# Sheet3.net
KiCad netlist of a schematic drawn in Altium Designer
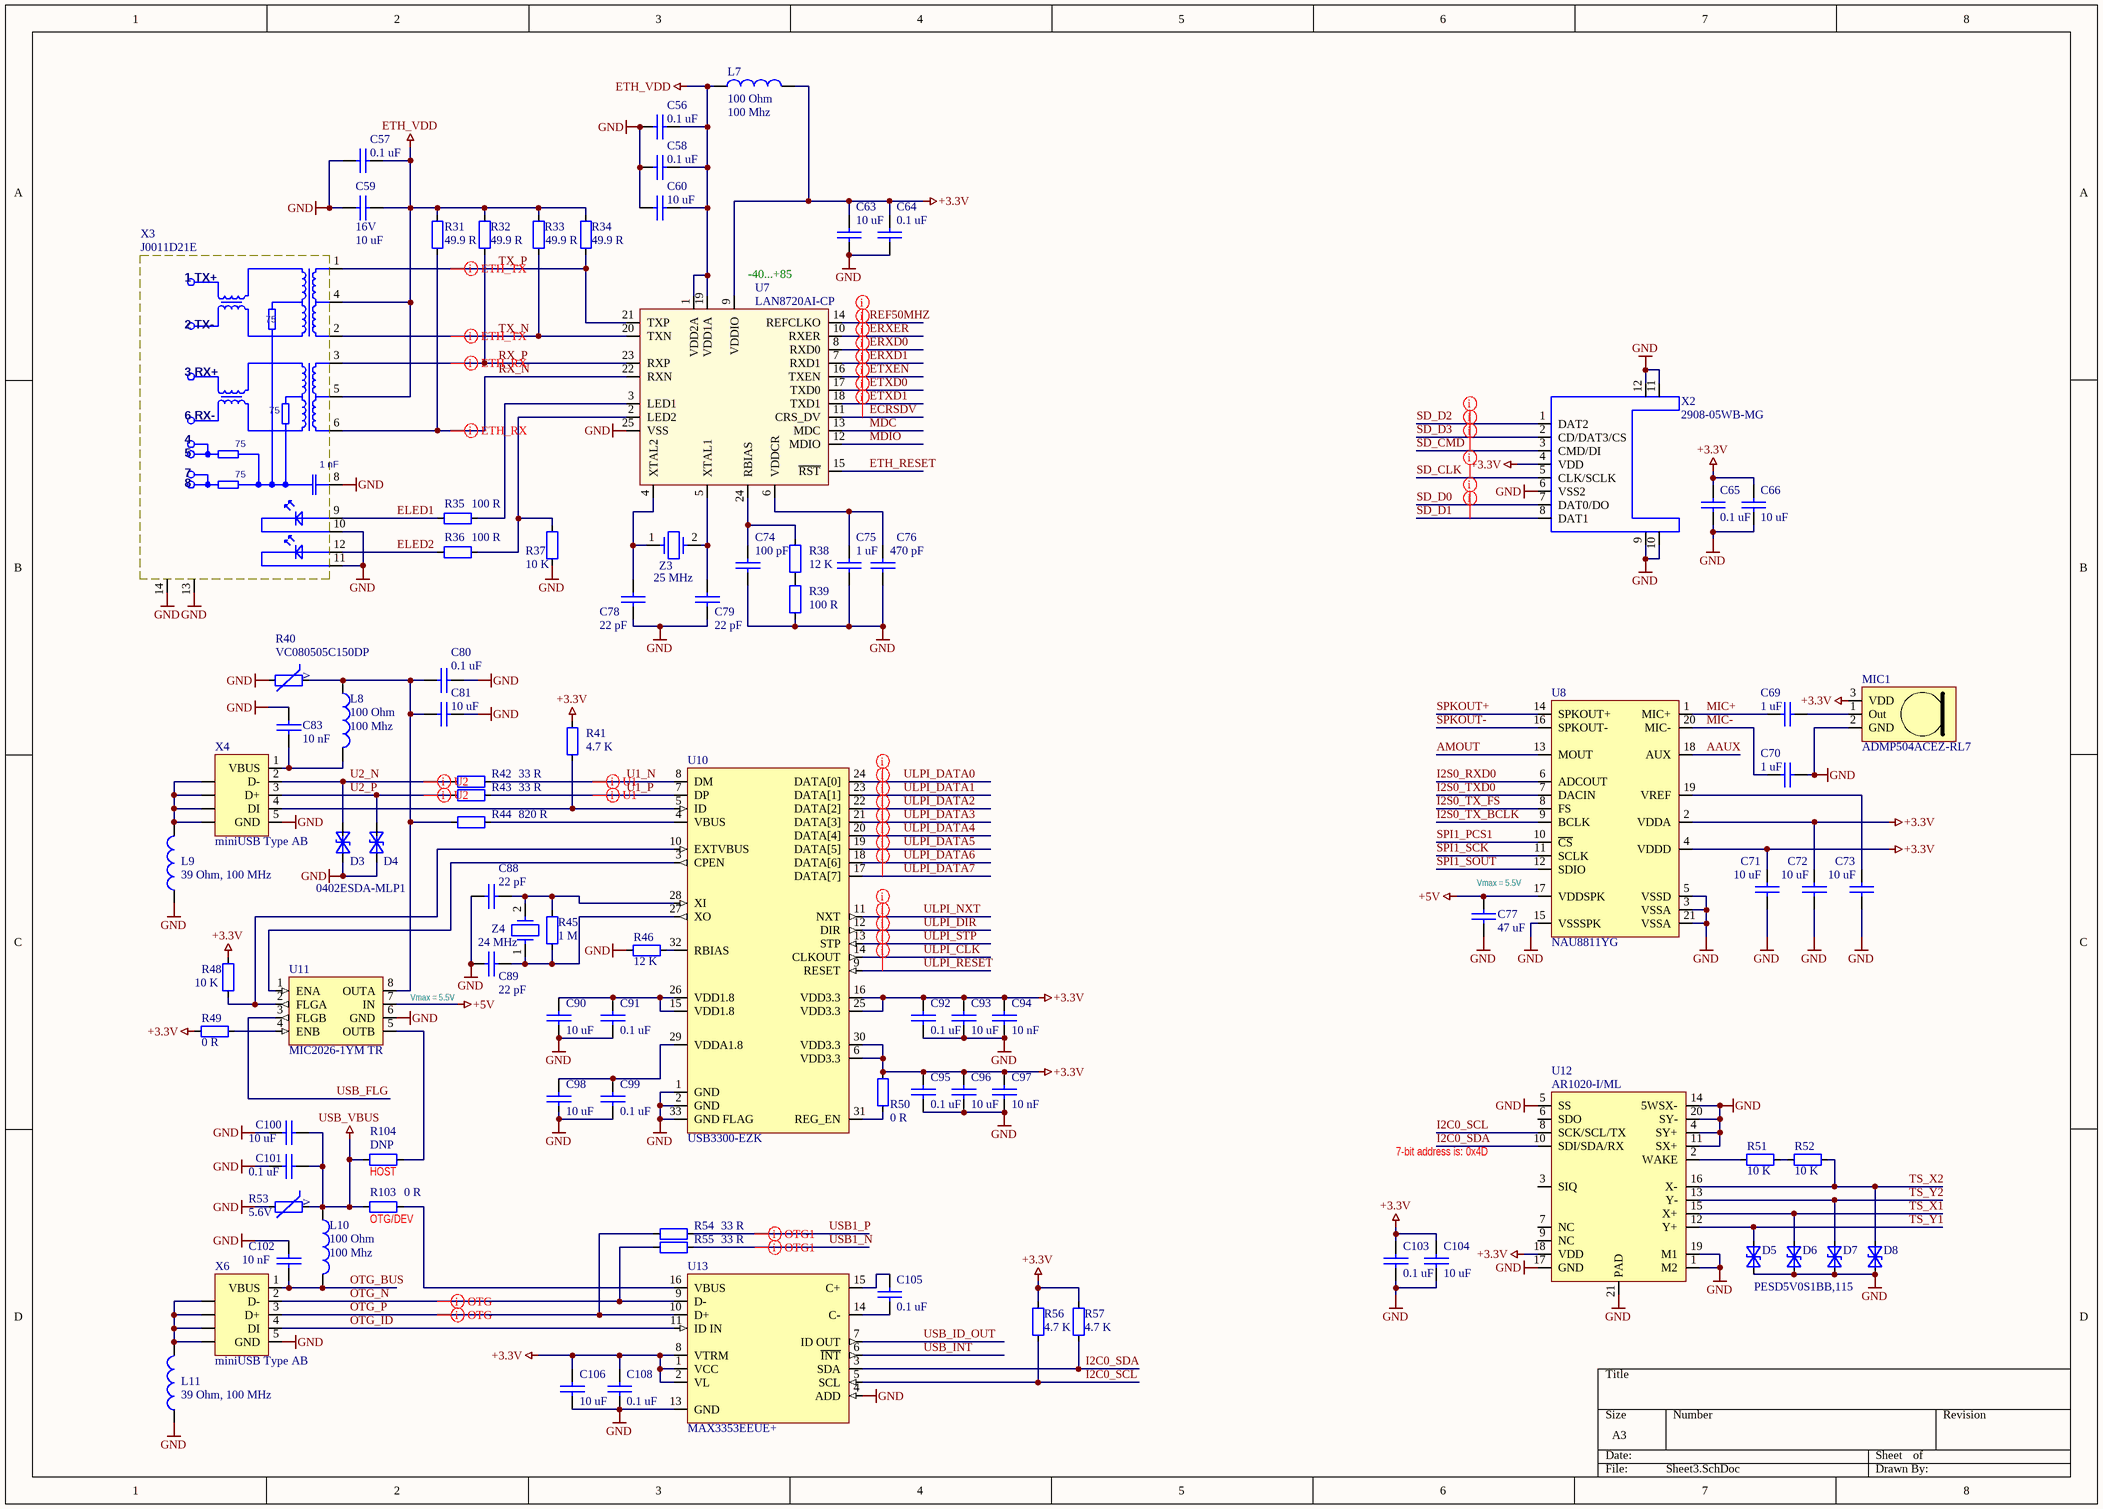
[diagram p0: Sheet3.SchDoc]

(export (version "E")
  (design (tool "Eeschema 10.0.6"))
  (components
    (comp (ref "C56")
      (value "0.1 uF")
      (footprint "1608[0603]")
      (description "0.1 uF, 25V, 10% , X7R,  0603 SMD MLC Capacitor")
      (fields (field (name "TOLERANCE") "10%") (field (name "MANUFACTURER") "SAMSUNG"))
      (libsource (lib "ea_Capacitors") (part "CVNF100K0603-25"))
    )
    (comp (ref "C57")
      (value "0.1 uF")
      (footprint "1608[0603]")
      (description "0.1 uF, 25V, 10% , X7R,  0603 SMD MLC Capacitor")
      (fields (field (name "TOLERANCE") "10%") (field (name "MANUFACTURER") "SAMSUNG"))
      (libsource (lib "ea_Capacitors") (part "CVNF100K0603-25"))
    )
    (comp (ref "C58")
      (value "0.1 uF")
      (footprint "1608[0603]")
      (description "0.1 uF, 25V, 10% , X7R,  0603 SMD MLC Capacitor")
      (fields (field (name "TOLERANCE") "10%") (field (name "MANUFACTURER") "SAMSUNG"))
      (libsource (lib "ea_Capacitors") (part "CVNF100K0603-25"))
    )
    (comp (ref "C59")
      (value "10 uF")
      (footprint "2012[0805]")
      (description "10 uF, 16V, X5R, ±10%, 0805")
      (fields
        (field (name "MANUFACTURER") "TDK Corporation")
        (field (name "TOLERANCE") "±10%")
        (field (name "VOLTAGE") "16V")
      )
      (libsource (lib "ea_Capacitors") (part "C2012X5R1C106K/0.85"))
    )
    (comp (ref "C60")
      (value "10 uF")
      (footprint "2012[0805]")
      (description "10 uF, 16V, X5R, ±10%, 0805")
      (fields (field (name "MANUFACTURER") "TDK Corporation") (field (name "TOLERANCE") "±10%"))
      (libsource (lib "ea_Capacitors") (part "C2012X5R1C106K/0.85"))
    )
    (comp (ref "C63")
      (value "10 uF")
      (footprint "2012[0805]")
      (description "10 uF, 16V, X5R, ±10%, 0805")
      (fields (field (name "MANUFACTURER") "TDK Corporation") (field (name "TOLERANCE") "±10%"))
      (libsource (lib "ea_Capacitors") (part "C2012X5R1C106K/0.85"))
    )
    (comp (ref "C64")
      (value "0.1 uF")
      (footprint "1608[0603]")
      (description "0.1 uF, 25V, 10% , X7R,  0603 SMD MLC Capacitor")
      (fields (field (name "TOLERANCE") "10%") (field (name "MANUFACTURER") "SAMSUNG"))
      (libsource (lib "ea_Capacitors") (part "CVNF100K0603-25"))
    )
    (comp (ref "C65")
      (value "0.1 uF")
      (footprint "1608[0603]")
      (description "0.1 uF, 25V, 10% , X7R,  0603 SMD MLC Capacitor")
      (fields (field (name "TOLERANCE") "10%") (field (name "MANUFACTURER") "SAMSUNG"))
      (libsource (lib "ea_Capacitors") (part "CVNF100K0603-25"))
    )
    (comp (ref "C66")
      (value "10 uF")
      (footprint "2012[0805]")
      (description "10 uF, 16V, X5R, ±10%, 0805")
      (fields (field (name "MANUFACTURER") "TDK Corporation") (field (name "TOLERANCE") "±10%"))
      (libsource (lib "ea_Capacitors") (part "C2012X5R1C106K/0.85"))
    )
    (comp (ref "C69")
      (value "1 uF")
      (footprint "2012[0805]")
      (description "1 uF, 10V, 10%, X7R, 0805")
      (fields (field (name "MANUFACTURER") "Murata") (field (name "TOLERANCE") "10%"))
      (libsource (lib "ea_Capacitors") (part "GRM21BR71A105KA01L"))
    )
    (comp (ref "C70")
      (value "1 uF")
      (footprint "2012[0805]")
      (description "1 uF, 10V, 10%, X7R, 0805")
      (fields (field (name "MANUFACTURER") "Murata") (field (name "TOLERANCE") "10%"))
      (libsource (lib "ea_Capacitors") (part "GRM21BR71A105KA01L"))
    )
    (comp (ref "C71")
      (value "10 uF")
      (footprint "0805-1206")
      (description "10 uF, 10V, Y5V, -20%.. +80%, 0805")
      (fields (field (name "MANUFACTURER") "Taiyo Yuden") (field (name "TOLERANCE") "20%.. +80%"))
      (libsource (lib "ea_Capacitors") (part "LMK212F106ZG-T"))
    )
    (comp (ref "C72")
      (value "10 uF")
      (footprint "0805-1206")
      (description "10 uF, 10V, Y5V, -20%.. +80%, 0805")
      (fields (field (name "MANUFACTURER") "Taiyo Yuden") (field (name "TOLERANCE") "20%.. +80%"))
      (libsource (lib "ea_Capacitors") (part "LMK212F106ZG-T"))
    )
    (comp (ref "C73")
      (value "10 uF")
      (footprint "0805-1206")
      (description "10 uF, 10V, Y5V, -20%.. +80%, 0805")
      (fields (field (name "MANUFACTURER") "Taiyo Yuden") (field (name "TOLERANCE") "20%.. +80%"))
      (libsource (lib "ea_Capacitors") (part "LMK212F106ZG-T"))
    )
    (comp (ref "C74")
      (value "100 pF")
      (footprint "1608[0603]")
      (description "100 pF, 50V, 5%, NP0, 0603 SMD MLC Capacitor")
      (fields (field (name "MANUFACTURER") "SAMSUNG") (field (name "TOLERANCE") "5%"))
      (libsource (lib "ea_Capacitors") (part "CCPF100K0603"))
    )
    (comp (ref "C75")
      (value "1 uF")
      (footprint "1608[0603]")
      (description "1.0 uF, 16V, 10%, X5R, 0603")
      (fields (field (name "TOLERANCE") "10%") (field (name "MANUFACTURER") "SAMSUNG"))
      (libsource (lib "*") (part "GRM188R60J105KA01D"))
    )
    (comp (ref "C76")
      (value "470 pF")
      (footprint "1608[0603]")
      (description "470 pF, 50V, 5%, C0G, NP0, -55°C ~ 125°C,0603 SMD MLC Capacitor")
      (fields (field (name "MANUFACTURER") "SAMSUNG") (field (name "TOLERANCE") "5%"))
      (libsource (lib "ea_Capacitors") (part "06035A471JAT2A"))
    )
    (comp (ref "C77")
      (value "47 uF")
      (footprint "3225[1210]")
      (description "47.0 uF, 10V, 10%, X7R, 1210")
      (fields
        (field (name "MANUFACTURER") "Murata Electronics North America")
        (field (name "TOLERANCE") "10%")
      )
      (libsource (lib "ea_Capacitors") (part "GRM32ER71A476KE15L"))
    )
    (comp (ref "C78")
      (value "22 pF")
      (footprint "1608[0603]")
      (description "22 pF, 50V, 5%, NP0, 0603 SMD MLC Capacitor")
      (fields (field (name "MANUFACTURER") "WLS") (field (name "TOLERANCE") "5%"))
      (libsource (lib "ea_Capacitors") (part "CCPF022K0603"))
    )
    (comp (ref "C79")
      (value "22 pF")
      (footprint "1608[0603]")
      (description "22 pF, 50V, 5%, NP0, 0603 SMD MLC Capacitor")
      (fields (field (name "MANUFACTURER") "WLS") (field (name "TOLERANCE") "5%"))
      (libsource (lib "ea_Capacitors") (part "CCPF022K0603"))
    )
    (comp (ref "C80")
      (value "0.1 uF")
      (footprint "1608[0603]")
      (description "0.1 uF, 25V, 10% , X7R,  0603 SMD MLC Capacitor")
      (fields (field (name "TOLERANCE") "10%") (field (name "MANUFACTURER") "SAMSUNG"))
      (libsource (lib "ea_Capacitors") (part "CVNF100K0603-25"))
    )
    (comp (ref "C81")
      (value "10 uF")
      (footprint "2012[0805]")
      (description "10 uF, 16V, X5R, ±10%, 0805")
      (fields (field (name "MANUFACTURER") "TDK Corporation") (field (name "TOLERANCE") "±10%"))
      (libsource (lib "ea_Capacitors") (part "C2012X5R1C106K/0.85"))
    )
    (comp (ref "C83")
      (value "10 nF")
      (footprint "1608[0603]")
      (description "10 nF, 50V, 5%, X7R, 0603 SMD MLC Capacitor")
      (fields (field (name "TOLERANCE") "5%") (field (name "MANUFACTURER") "SAMSUNG"))
      (libsource (lib "ea_Capacitors") (part "CVNF010K0603"))
    )
    (comp (ref "C88")
      (value "22 pF")
      (footprint "1608[0603]")
      (description "22 pF, 50V, 5%, NP0, 0603 SMD MLC Capacitor")
      (fields (field (name "MANUFACTURER") "WLS") (field (name "TOLERANCE") "5%"))
      (libsource (lib "ea_Capacitors") (part "CCPF022K0603"))
    )
    (comp (ref "C89")
      (value "22 pF")
      (footprint "1608[0603]")
      (description "22 pF, 50V, 5%, NP0, 0603 SMD MLC Capacitor")
      (fields (field (name "MANUFACTURER") "WLS") (field (name "TOLERANCE") "5%"))
      (libsource (lib "ea_Capacitors") (part "CCPF022K0603"))
    )
    (comp (ref "C90")
      (value "10 uF")
      (footprint "2012[0805]")
      (description "10 uF, 16V, X5R, ±10%, 0805")
      (fields (field (name "MANUFACTURER") "TDK Corporation") (field (name "TOLERANCE") "±10%"))
      (libsource (lib "ea_Capacitors") (part "C2012X5R1C106K/0.85"))
    )
    (comp (ref "C91")
      (value "0.1 uF")
      (footprint "1608[0603]")
      (description "0.1 uF, 25V, 10% , X7R,  0603 SMD MLC Capacitor")
      (fields (field (name "TOLERANCE") "10%") (field (name "MANUFACTURER") "SAMSUNG"))
      (libsource (lib "ea_Capacitors") (part "CVNF100K0603-25"))
    )
    (comp (ref "C92")
      (value "0.1 uF")
      (footprint "1608[0603]")
      (description "0.1 uF, 25V, 10% , X7R,  0603 SMD MLC Capacitor")
      (fields (field (name "TOLERANCE") "10%") (field (name "MANUFACTURER") "SAMSUNG"))
      (libsource (lib "ea_Capacitors") (part "CVNF100K0603-25"))
    )
    (comp (ref "C93")
      (value "10 uF")
      (footprint "2012[0805]")
      (description "10 uF, 16V, X5R, ±10%, 0805")
      (fields (field (name "MANUFACTURER") "TDK Corporation") (field (name "TOLERANCE") "±10%"))
      (libsource (lib "ea_Capacitors") (part "C2012X5R1C106K/0.85"))
    )
    (comp (ref "C94")
      (value "10 nF")
      (footprint "1005[0402]")
      (description "10 nF, 16V, 10%, X7R, 0402")
      (fields (field (name "TOLERANCE") "10%") (field (name "MANUFACTURER") "SAMSUNG"))
      (libsource (lib "ea_Capacitors") (part "GRM155R71C103KA01D"))
    )
    (comp (ref "C95")
      (value "0.1 uF")
      (footprint "1608[0603]")
      (description "0.1 uF, 25V, 10% , X7R,  0603 SMD MLC Capacitor")
      (fields (field (name "TOLERANCE") "10%") (field (name "MANUFACTURER") "SAMSUNG"))
      (libsource (lib "ea_Capacitors") (part "CVNF100K0603-25"))
    )
    (comp (ref "C96")
      (value "10 uF")
      (footprint "2012[0805]")
      (description "10 uF, 16V, X5R, ±10%, 0805")
      (fields (field (name "MANUFACTURER") "TDK Corporation") (field (name "TOLERANCE") "±10%"))
      (libsource (lib "ea_Capacitors") (part "C2012X5R1C106K/0.85"))
    )
    (comp (ref "C97")
      (value "10 nF")
      (footprint "1005[0402]")
      (description "10 nF, 16V, 10%, X7R, 0402")
      (fields (field (name "TOLERANCE") "10%") (field (name "MANUFACTURER") "SAMSUNG"))
      (libsource (lib "ea_Capacitors") (part "GRM155R71C103KA01D"))
    )
    (comp (ref "C98")
      (value "10 uF")
      (footprint "2012[0805]")
      (description "10 uF, 16V, X5R, ±10%, 0805")
      (fields (field (name "MANUFACTURER") "TDK Corporation") (field (name "TOLERANCE") "±10%"))
      (libsource (lib "ea_Capacitors") (part "C2012X5R1C106K/0.85"))
    )
    (comp (ref "C99")
      (value "0.1 uF")
      (footprint "1608[0603]")
      (description "0.1 uF, 25V, 10% , X7R,  0603 SMD MLC Capacitor")
      (fields (field (name "TOLERANCE") "10%") (field (name "MANUFACTURER") "SAMSUNG"))
      (libsource (lib "ea_Capacitors") (part "CVNF100K0603-25"))
    )
    (comp (ref "C100")
      (value "10 uF")
      (footprint "2012[0805]")
      (description "10 uF, 16V, X5R, ±10%, 0805")
      (fields (field (name "MANUFACTURER") "TDK Corporation") (field (name "TOLERANCE") "±10%"))
      (libsource (lib "ea_Capacitors") (part "C2012X5R1C106K/0.85"))
    )
    (comp (ref "C101")
      (value "0.1 uF")
      (footprint "1608[0603]")
      (description "0.1 uF, 25V, 10% , X7R,  0603 SMD MLC Capacitor")
      (fields (field (name "TOLERANCE") "10%") (field (name "MANUFACTURER") "SAMSUNG"))
      (libsource (lib "ea_Capacitors") (part "CVNF100K0603-25"))
    )
    (comp (ref "C102")
      (value "10 nF")
      (footprint "1608[0603]")
      (description "10 nF, 50V, 5%, X7R, 0603 SMD MLC Capacitor")
      (fields (field (name "TOLERANCE") "5%") (field (name "MANUFACTURER") "SAMSUNG"))
      (libsource (lib "ea_Capacitors") (part "CVNF010K0603"))
    )
    (comp (ref "C103")
      (value "0.1 uF")
      (footprint "1608[0603]")
      (description "0.1 uF, 25V, 10% , X7R,  0603 SMD MLC Capacitor")
      (fields (field (name "TOLERANCE") "10%") (field (name "MANUFACTURER") "SAMSUNG"))
      (libsource (lib "ea_Capacitors") (part "CVNF100K0603-25"))
    )
    (comp (ref "C104")
      (value "10 uF")
      (footprint "2012[0805]")
      (description "10 uF, 16V, X5R, ±10%, 0805")
      (fields (field (name "MANUFACTURER") "TDK Corporation") (field (name "TOLERANCE") "±10%"))
      (libsource (lib "ea_Capacitors") (part "C2012X5R1C106K/0.85"))
    )
    (comp (ref "C105")
      (value "0.1 uF")
      (footprint "1608[0603]")
      (description "0.1 uF, 25V, 10% , X7R,  0603 SMD MLC Capacitor")
      (fields (field (name "TOLERANCE") "10%") (field (name "MANUFACTURER") "SAMSUNG"))
      (libsource (lib "ea_Capacitors") (part "CVNF100K0603-25"))
    )
    (comp (ref "C106")
      (value "10 uF")
      (footprint "2012[0805]")
      (description "10 uF, 16V, X5R, ±10%, 0805")
      (fields (field (name "MANUFACTURER") "TDK Corporation") (field (name "TOLERANCE") "±10%"))
      (libsource (lib "ea_Capacitors") (part "C2012X5R1C106K/0.85"))
    )
    (comp (ref "C108")
      (value "0.1 uF")
      (footprint "1608[0603]")
      (description "0.1 uF, 25V, 10% , X7R,  0603 SMD MLC Capacitor")
      (fields (field (name "TOLERANCE") "10%") (field (name "MANUFACTURER") "SAMSUNG"))
      (libsource (lib "ea_Capacitors") (part "CVNF100K0603-25"))
    )
    (comp (ref "D3")
      (value "0402ESDA-MLP1")
      (footprint "0402")
      (description "SUPPRESSOR ESD 30VDC 0402 HFREE")
      (fields (field (name "MANUFACTURER") "Cooper Bussmann") (field (name "PARTNUM") "283-2964-2-ND"))
      (libsource (lib "ea_TVS_protection") (part "0402ESDA-MLP1"))
    )
    (comp (ref "D4")
      (value "0402ESDA-MLP1")
      (footprint "0402")
      (description "SUPPRESSOR ESD 30VDC 0402 HFREE")
      (fields (field (name "MANUFACTURER") "Cooper Bussmann") (field (name "PARTNUM") "283-2964-2-ND"))
      (libsource (lib "ea_TVS_protection") (part "0402ESDA-MLP1"))
    )
    (comp (ref "D5")
      (value "PESD5V0S1BB,115")
      (footprint "SOD523")
      (description "TVS DIODE 5VWM 14VC SOD523")
      (fields (field (name "MANUFACTURER") "NXP Semiconductors") (field (name "PARTNUM") "568-4054-2-ND"))
      (libsource (lib "ea_TVS_protection") (part "PESD5V0S1BB,115"))
    )
    (comp (ref "D6")
      (value "PESD5V0S1BB,115")
      (footprint "SOD523")
      (description "TVS DIODE 5VWM 14VC SOD523")
      (fields (field (name "MANUFACTURER") "NXP Semiconductors") (field (name "PARTNUM") "568-4054-2-ND"))
      (libsource (lib "ea_TVS_protection") (part "PESD5V0S1BB,115"))
    )
    (comp (ref "D7")
      (value "PESD5V0S1BB,115")
      (footprint "SOD523")
      (description "TVS DIODE 5VWM 14VC SOD523")
      (fields (field (name "MANUFACTURER") "NXP Semiconductors") (field (name "PARTNUM") "568-4054-2-ND"))
      (libsource (lib "ea_TVS_protection") (part "PESD5V0S1BB,115"))
    )
    (comp (ref "D8")
      (value "PESD5V0S1BB,115")
      (footprint "SOD523")
      (description "TVS DIODE 5VWM 14VC SOD523")
      (fields (field (name "MANUFACTURER") "NXP Semiconductors") (field (name "PARTNUM") "568-4054-2-ND"))
      (libsource (lib "ea_TVS_protection") (part "PESD5V0S1BB,115"))
    )
    (comp (ref "L7")
      (value "100 Ohm")
      (footprint "0603")
      (description "FERRITE CHIP 100 OHM 1A 0603")
      (fields
        (field (name "MANUFACTURER") "TDK Corporation")
        (field (name "PARTNUM") "445-2988-2-ND")
        (field (name "FREQ") "100 Mhz")
      )
      (libsource (lib "ea_Inductors") (part "MPZ1608D101B"))
    )
    (comp (ref "L8")
      (value "100 Ohm")
      (footprint "0603")
      (description "FERRITE CHIP 100 OHM 1A 0603")
      (fields
        (field (name "MANUFACTURER") "TDK Corporation")
        (field (name "PARTNUM") "445-2988-2-ND")
        (field (name "FREQ") "100 Mhz")
      )
      (libsource (lib "ea_Inductors") (part "MPZ1608D101B"))
    )
    (comp (ref "L9")
      (value "39 Ohm, 100 MHz")
      (footprint "0805")
      (description "Ferrite bead, 39 Ohm, 100 MHz,  4 A")
      (fields (field (name "MANUFACTURER") "Panasonic - ECG") (field (name "PARTNUM") "P10191TR-ND"))
      (libsource (lib "*") (part "EXC-ML20A390U"))
    )
    (comp (ref "L10")
      (value "100 Ohm")
      (footprint "0603")
      (description "FERRITE CHIP 100 OHM 1A 0603")
      (fields
        (field (name "MANUFACTURER") "TDK Corporation")
        (field (name "PARTNUM") "445-2988-2-ND")
        (field (name "FREQ") "100 Mhz")
      )
      (libsource (lib "ea_Inductors") (part "MPZ1608D101B"))
    )
    (comp (ref "L11")
      (value "39 Ohm, 100 MHz")
      (footprint "0805")
      (description "Ferrite bead, 39 Ohm, 100 MHz,  4 A")
      (fields (field (name "MANUFACTURER") "Panasonic - ECG") (field (name "PARTNUM") "P10191TR-ND"))
      (libsource (lib "*") (part "EXC-ML20A390U"))
    )
    (comp (ref "MIC1")
      (value "ADMP504ACEZ-RL7")
      (footprint "ADMP504ACEZ")
      (description "Mems Omni  -38dB ,  100Hz-20kHz, 200Ohm, 2 V, 65dB s/n, 225 uA")
      (fields
        (field (name "MANUFACTURER") "Analog Devices Inc")
        (field (name "PARTNUM") "ADMP504ACEZ-RL7CT-ND")
      )
      (libsource (lib "ea_Sound_devices") (part "ADMP504ACEZ-RL7"))
    )
    (comp (ref "R31")
      (value "49.9 R")
      (footprint "0603")
      (description "49.9 R, 1%, 0.1 W, 0603, SMD Resistor, Taped")
      (fields (field (name "MANUFACTURER") "PANASONIC") (field (name "TOLERANCE") "1%"))
      (libsource (lib "") (part "CRCW060349R9FKEA_1"))
    )
    (comp (ref "R32")
      (value "49.9 R")
      (footprint "0603")
      (description "49.9 R, 1%, 0.1 W, 0603, SMD Resistor, Taped")
      (fields (field (name "MANUFACTURER") "PANASONIC") (field (name "TOLERANCE") "1%"))
      (libsource (lib "") (part "CRCW060349R9FKEA_1"))
    )
    (comp (ref "R33")
      (value "49.9 R")
      (footprint "0603")
      (description "49.9 R, 1%, 0.1 W, 0603, SMD Resistor, Taped")
      (fields (field (name "MANUFACTURER") "PANASONIC") (field (name "TOLERANCE") "1%"))
      (libsource (lib "*") (part "CRCW060349R9FKEA"))
    )
    (comp (ref "R34")
      (value "49.9 R")
      (footprint "0603")
      (description "49.9 R, 1%, 0.1 W, 0603, SMD Resistor, Taped")
      (fields (field (name "MANUFACTURER") "PANASONIC") (field (name "TOLERANCE") "1%"))
      (libsource (lib "*") (part "CRCW060349R9FKEA"))
    )
    (comp (ref "R35")
      (value "100 R")
      (footprint "0603")
      (description "100 R, 1%, 0603, SMD Resistor, Taped")
      (fields (field (name "MANUFACTURER") "PANASONIC") (field (name "TOLERANCE") "1%"))
      (libsource (lib "ea_Resistors") (part "RL0603E100-1"))
    )
    (comp (ref "R36")
      (value "100 R")
      (footprint "0603")
      (description "100 R, 1%, 0603, SMD Resistor, Taped")
      (fields (field (name "MANUFACTURER") "PANASONIC") (field (name "TOLERANCE") "1%"))
      (libsource (lib "ea_Resistors") (part "RL0603E100-1"))
    )
    (comp (ref "R37")
      (value "10 K")
      (footprint "0603")
      (description "10 K, 1%, 0603, SMD Resistor, Taped")
      (fields (field (name "MANUFACTURER") "PANASONIC") (field (name "TOLERANCE") "1%"))
      (libsource (lib "") (part "RL0603K010-1_2"))
    )
    (comp (ref "R38")
      (value "12 K")
      (footprint "0603")
      (description "12 K, 1%, 0603, SMD Resistor, Taped")
      (fields (field (name "MANUFACTURER") "YAGEO AMERICA CORPORATION") (field (name "TOLERANCE") "1%"))
      (libsource (lib "ea_Resistors") (part "RL0603K012-1"))
    )
    (comp (ref "R39")
      (value "100 R")
      (footprint "0603")
      (description "100 R, 1%, 0603, SMD Resistor, Taped")
      (fields (field (name "MANUFACTURER") "PANASONIC") (field (name "TOLERANCE") "1%"))
      (libsource (lib "") (part "RL0603E100-1_1"))
    )
    (comp (ref "R40")
      (value "VC080505C150DP")
      (footprint "2012[0805]")
      (description "TVS, volt 5.6 V, Clamping voltage 18 V")
      (fields (field (name "MANUFACTURER") "AVX Corporation") (field (name "PARTNUM") "478-2507-1-ND"))
      (libsource (lib "ea_TVS_protection") (part "VC080505C150D"))
    )
    (comp (ref "R41")
      (value "4.7 K")
      (footprint "0603")
      (description "4.7 K, 1%, 0603, SMD Resistor, Taped")
      (fields (field (name "MANUFACTURER") "YAGEO AMERICA CORPORATION") (field (name "TOLERANCE") "1%"))
      (libsource (lib "ea_Resistors") (part "RL0603K004.7-1_1"))
    )
    (comp (ref "R42")
      (value "33 R")
      (footprint "0603")
      (description "33 R, 1%, 0603, SMD Resistor, Taped")
      (fields (field (name "MANUFACTURER") "YAGEO AMERICA CORPORATION") (field (name "TOLERANCE") "1%"))
      (libsource (lib "ea_Resistors") (part "RL0603E033-1"))
    )
    (comp (ref "R43")
      (value "33 R")
      (footprint "0603")
      (description "33 R, 1%, 0603, SMD Resistor, Taped")
      (fields (field (name "MANUFACTURER") "YAGEO AMERICA CORPORATION") (field (name "TOLERANCE") "1%"))
      (libsource (lib "ea_Resistors") (part "RL0603E033-1"))
    )
    (comp (ref "R44")
      (value "820 R")
      (footprint "0603")
      (description "820 R, 1%, 0603, SMD Resistor, Taped")
      (fields (field (name "MANUFACTURER") "YAGEO AMERICA CORPORATION") (field (name "TOLERANCE") "1%"))
      (libsource (lib "ea_Resistors") (part "RC0603FR-07820RL"))
    )
    (comp (ref "R45")
      (value "1 M")
      (footprint "0603")
      (description "1 M, 1%, 0603, SMD Resistor, Taped")
      (fields (field (name "MANUFACTURER") "YAGEO AMERICA CORPORATION") (field (name "TOLERANCE") "1%"))
      (libsource (lib "ea_Resistors") (part "RC0603FR-071ML"))
    )
    (comp (ref "R46")
      (value "12 K")
      (footprint "0603")
      (description "12 K, 1%, 0603, SMD Resistor, Taped")
      (fields (field (name "MANUFACTURER") "YAGEO AMERICA CORPORATION") (field (name "TOLERANCE") "1%"))
      (libsource (lib "ea_Resistors") (part "RL0603K012-1_1"))
    )
    (comp (ref "R48")
      (value "10 K")
      (footprint "0603")
      (description "10 K, 1%, 0603, SMD Resistor, Taped")
      (fields (field (name "MANUFACTURER") "PANASONIC") (field (name "TOLERANCE") "1%"))
      (libsource (lib "") (part "RL0603K010-1_1"))
    )
    (comp (ref "R49")
      (value "0 R")
      (footprint "0603")
      (description "0 R, 5%, 0603, SMD Resistor, Taped")
      (fields (field (name "MANUFACTURER") "YAGEO AMERICA CORPORATION") (field (name "TOLERANCE") "5%"))
      (libsource (lib "ea_Resistors") (part "RL0603E000"))
    )
    (comp (ref "R50")
      (value "0 R")
      (footprint "0603")
      (description "0 R, 5%, 0603, SMD Resistor, Taped")
      (fields (field (name "MANUFACTURER") "YAGEO AMERICA CORPORATION") (field (name "TOLERANCE") "5%"))
      (libsource (lib "") (part "RL0603E000_1"))
    )
    (comp (ref "R51")
      (value "10 K")
      (footprint "0603")
      (description "10 K, 1%, 0603, SMD Resistor, Taped")
      (fields (field (name "MANUFACTURER") "PANASONIC") (field (name "TOLERANCE") "1%"))
      (libsource (lib "ea_Resistors") (part "RL0603K010-1"))
    )
    (comp (ref "R52")
      (value "10 K")
      (footprint "0603")
      (description "10 K, 1%, 0603, SMD Resistor, Taped")
      (fields (field (name "MANUFACTURER") "PANASONIC") (field (name "TOLERANCE") "1%"))
      (libsource (lib "ea_Resistors") (part "RL0603K010-1"))
    )
    (comp (ref "R53")
      (value "VC080505C150DP")
      (footprint "2012[0805]")
      (description "TVS, volt 5.6 V, Clamping voltage 18 V")
      (fields
        (field (name "MANUFACTURER") "AVX Corporation")
        (field (name "PARTNUM") "478-2507-1-ND")
        (field (name "VOLTAGE") "5.6V")
      )
      (libsource (lib "ea_TVS_protection") (part "VC080505C150D"))
    )
    (comp (ref "R54")
      (value "33 R")
      (footprint "0603")
      (description "33 R, 1%, 0603, SMD Resistor, Taped")
      (fields (field (name "MANUFACTURER") "YAGEO AMERICA CORPORATION") (field (name "TOLERANCE") "1%"))
      (libsource (lib "ea_Resistors") (part "RL0603E033-1"))
    )
    (comp (ref "R55")
      (value "33 R")
      (footprint "0603")
      (description "33 R, 1%, 0603, SMD Resistor, Taped")
      (fields (field (name "MANUFACTURER") "YAGEO AMERICA CORPORATION") (field (name "TOLERANCE") "1%"))
      (libsource (lib "ea_Resistors") (part "RL0603E033-1"))
    )
    (comp (ref "R56")
      (value "4.7 K")
      (footprint "0603")
      (description "4.7 K, 1%, 0603, SMD Resistor, Taped")
      (fields (field (name "MANUFACTURER") "YAGEO AMERICA CORPORATION") (field (name "TOLERANCE") "1%"))
      (libsource (lib "ea_Resistors") (part "RL0603K004.7-1_1"))
    )
    (comp (ref "R57")
      (value "4.7 K")
      (footprint "0603")
      (description "4.7 K, 1%, 0603, SMD Resistor, Taped")
      (fields (field (name "MANUFACTURER") "YAGEO AMERICA CORPORATION") (field (name "TOLERANCE") "1%"))
      (libsource (lib "ea_Resistors") (part "RL0603K004.7-1_1"))
    )
    (comp (ref "R103")
      (value "0 R")
      (footprint "0603")
      (description "0 R, 5%, 0603, SMD Resistor, Taped")
      (fields (field (name "MANUFACTURER") "YAGEO AMERICA CORPORATION") (field (name "TOLERANCE") "5%"))
      (libsource (lib "ea_Resistors") (part "RL0603E000"))
    )
    (comp (ref "R104")
      (value "DNP")
      (footprint "0603")
      (description "DNP, 0603")
      (fields (field (name "Comment") "DNP_0603"))
      (libsource (lib "ea_Resistors") (part "DNP_0603"))
    )
    (comp (ref "U7")
      (value "LAN8720AI-CP")
      (footprint "THIN QFN 24")
      (description "TXRX PHY 10/100 1.6...3.6V, -40..85 C, 24-QFN")
      (fields (field (name "MANUFACTURER") "Micrel Inc") (field (name "PARTNUM") "886-LAN8720AI-CP"))
      (libsource (lib "ea_IC_Interfaces") (part "LAN8720AI-CP"))
    )
    (comp (ref "U8")
      (value "NAU8811YG")
      (footprint "THIN QFN 20 W/O VIA")
      (description "Audio CODEC, Mono, Speaker Driver, QFN-20")
      (fields (field (name "MANUFACTURER") "Nuvoton Technology") (field (name "PARTNUM") "NAU8811YG-ND"))
      (libsource (lib "ea_IC_audio") (part "NAU8811YG"))
    )
    (comp (ref "U10")
      (value "USB3300-EZK")
      (footprint "HVQFN32 NXP")
      (description "IC USB HOST/OTG PHY ULPI 32-QFN")
      (fields (field (name "MANUFACTURER") "Microchip Technology") (field (name "PARTNUM") "638-1034-ND"))
      (libsource (lib "ea_IC_Interfaces") (part "USB3300-EZK"))
    )
    (comp (ref "U11")
      (value "MIC2026-1YM TR")
      (footprint "SO-8")
      (description "Dual-Channel Power Distribution Switch, 8 Lead SOIC")
      (fields (field (name "MANUFACTURER") "Micrel") (field (name "PARTNUM") "576-1059-1-ND"))
      (libsource (lib "ea_USB") (part "MIC2026-1YM TR"))
    )
    (comp (ref "U12")
      (value "AR1020-I/ML")
      (footprint "THIN QFN 20 W/O VIA")
      (description "IC TOUCH SCREEN CTRLR 20-QFN")
      (fields (field (name "MANUFACTURER") "Microchip Technology") (field (name "PARTNUM") "AR1020-I/ML-ND"))
      (libsource (lib "ea_IC_Interfaces") (part "AR1020-I/ML"))
    )
    (comp (ref "U13")
      (value "MAX3353EEUE+")
      (footprint "TSOP65P640-16AM")
      (description "IC CHARGE PUMP USB OTG 16TSSOP")
      (fields (field (name "MANUFACTURER") "Maxim Integrated") (field (name "PARTNUM") "MAX3353EEUE+-ND"))
      (libsource (lib "ea_IC_Interfaces") (part "MAX3353EEUE+"))
    )
    (comp (ref "X2")
      (value "2908-05WB-MG")
      (footprint "2908-05WB-MG")
      (description "microSD cadr holder")
      (fields
        (field (name "MANUFACTURER") "Amphenol Commercial Products")
        (field (name "PARTNUM") "101-00660-68-6-1-ND")
      )
      (libsource (lib "ea_CARD_holders") (part "2908-05WB-MG"))
    )
    (comp (ref "X3")
      (value "J0011D21E")
      (footprint "PulseJack_J00")
      (description "10/100 Base-TX RJ45 1x1 with LEDs 8-pin (J0 series)")
      (fields (field (name "MANUFACTURER") "Pulse") (field (name "PARTNUM") "673-J0011D21E"))
      (libsource (lib "ea_Connectors") (part "J0011D21E"))
    )
    (comp (ref "X4")
      (value "miniUSB Type AB")
      (footprint "USB AB 56579-0576 Molex")
      (description "SMD USB - OTG, miniUSB Type AB")
      (fields
        (field (name "MANUFACTURER") "Molex/Waldom Electronics Corp")
        (field (name "PARTNUM") "WM17122CT-ND")
      )
      (libsource (lib "ea_Connectors") (part "USB AB 56579-0576"))
    )
    (comp (ref "X6")
      (value "miniUSB Type AB")
      (footprint "USB AB 56579-0576 Molex")
      (description "SMD USB - OTG, miniUSB Type AB")
      (fields
        (field (name "MANUFACTURER") "Molex/Waldom Electronics Corp")
        (field (name "PARTNUM") "WM17122CT-ND")
      )
      (libsource (lib "ea_Connectors") (part "USB AB 56579-0576"))
    )
    (comp (ref "Z3")
      (value "25 MHz")
      (footprint "ABM3")
      (description "25 MHz, 18 pF, 30 Ohm, ±50ppm, -20°C ~ 70°C")
      (fields (field (name "MANUFACTURER") "Abracon Corporation") (field (name "PARTNUM") "535-9108-1-ND"))
      (libsource (lib "ea_OSC_CLK_GEN") (part "ABM3-25.000MHZ-B2-T"))
    )
    (comp (ref "Z4")
      (value "24 MHz")
      (footprint "ABM3")
      (description "24 MHz, 18 pF, 30 Ohm, ±50ppm, -20°C ~ 70°C")
      (fields (field (name "MANUFACTURER") "Abracon Corporation") (field (name "PARTNUM") "535-9106-1-ND"))
      (libsource (lib "ea_OSC_CLK_GEN") (part "ABM3-24.000MHZ-B2-T"))
    )
  )
  (nets
    (net (code "1") (name "+3.3V") (class "Default")
      (node (ref "C103") (pin "1") (pinfunction "1_1") (pintype "passive"))
      (node (ref "C104") (pin "1") (pinfunction "1_1") (pintype "passive"))
      (node (ref "C106") (pin "2") (pinfunction "2_2") (pintype "passive"))
      (node (ref "C108") (pin "1") (pinfunction "1_1") (pintype "passive"))
      (node (ref "C63") (pin "2") (pinfunction "2_2") (pintype "passive"))
      (node (ref "C64") (pin "2") (pinfunction "2_2") (pintype "passive"))
      (node (ref "C65") (pin "1") (pinfunction "1_1") (pintype "passive"))
      (node (ref "C66") (pin "1") (pinfunction "1_1") (pintype "passive"))
      (node (ref "C71") (pin "2") (pinfunction "2_2") (pintype "passive"))
      (node (ref "C72") (pin "2") (pinfunction "2_2") (pintype "passive"))
      (node (ref "C92") (pin "2") (pinfunction "2_2") (pintype "passive"))
      (node (ref "C93") (pin "1") (pinfunction "1_1") (pintype "passive"))
      (node (ref "C94") (pin "2") (pinfunction "2_2") (pintype "passive"))
      (node (ref "C95") (pin "2") (pinfunction "2_2") (pintype "passive"))
      (node (ref "C96") (pin "1") (pinfunction "1_1") (pintype "passive"))
      (node (ref "C97") (pin "2") (pinfunction "2_2") (pintype "passive"))
      (node (ref "L7") (pin "2") (pinfunction "2_2") (pintype "passive"))
      (node (ref "MIC1") (pin "3") (pinfunction "VDD_3") (pintype "passive"))
      (node (ref "R41") (pin "2") (pinfunction "2_2") (pintype "passive"))
      (node (ref "R48") (pin "1") (pinfunction "1_1") (pintype "passive"))
      (node (ref "R49") (pin "2") (pinfunction "2_2") (pintype "passive"))
      (node (ref "R50") (pin "2") (pinfunction "2_2") (pintype "passive"))
      (node (ref "R56") (pin "2") (pinfunction "2_2") (pintype "passive"))
      (node (ref "R57") (pin "2") (pinfunction "2_2") (pintype "passive"))
      (node (ref "U10") (pin "16") (pinfunction "VDD3.3_16") (pintype "power_in"))
      (node (ref "U10") (pin "25") (pinfunction "VDD3.3_25") (pintype "power_in"))
      (node (ref "U10") (pin "30") (pinfunction "VDD3.3_30") (pintype "power_in"))
      (node (ref "U10") (pin "6") (pinfunction "VDD3.3_6") (pintype "power_in"))
      (node (ref "U12") (pin "18") (pinfunction "VDD_18") (pintype "passive"))
      (node (ref "U13") (pin "1") (pinfunction "VCC_1") (pintype "power_in"))
      (node (ref "U13") (pin "2") (pinfunction "VL_2") (pintype "power_in"))
      (node (ref "U13") (pin "8") (pinfunction "VTRM_8") (pintype "power_in"))
      (node (ref "U7") (pin "9") (pinfunction "VDDIO_9") (pintype "passive"))
      (node (ref "U8") (pin "2") (pinfunction "VDDA_2") (pintype "passive"))
      (node (ref "U8") (pin "4") (pinfunction "VDDD_4") (pintype "passive"))
      (node (ref "X2") (pin "4") (pinfunction "VDD_4") (pintype "passive"))
    )
    (net (code "2") (name "+5V") (class "Default")
      (node (ref "C77") (pin "1") (pinfunction "1_1") (pintype "passive"))
      (node (ref "U11") (pin "7") (pinfunction "IN_7") (pintype "passive"))
      (node (ref "U8") (pin "17") (pinfunction "VDDSPK_17") (pintype "passive"))
    )
    (net (code "3") (name "/AAUX") (class "Default")
      (node (ref "U8") (pin "18") (pinfunction "AUX_18") (pintype "passive"))
    )
    (net (code "4") (name "/AMOUT") (class "Default")
      (node (ref "U8") (pin "13") (pinfunction "MOUT_13") (pintype "passive"))
    )
    (net (code "5") (name "/ECRSDV") (class "Default")
      (node (ref "U7") (pin "11") (pinfunction "CRS_DV_11") (pintype "passive"))
    )
    (net (code "6") (name "/ELED1") (class "Default")
      (node (ref "R35") (pin "1") (pinfunction "1_1") (pintype "passive"))
      (node (ref "X3") (pin "9") (pinfunction "9_9") (pintype "passive"))
    )
    (net (code "7") (name "/ELED2") (class "Default")
      (node (ref "R36") (pin "1") (pinfunction "1_1") (pintype "passive"))
      (node (ref "X3") (pin "12") (pinfunction "12_12") (pintype "passive"))
    )
    (net (code "8") (name "/ERXD0") (class "Default")
      (node (ref "U7") (pin "8") (pinfunction "RXD0_8") (pintype "passive"))
    )
    (net (code "9") (name "/ERXD1") (class "Default")
      (node (ref "U7") (pin "7") (pinfunction "RXD1_7") (pintype "passive"))
    )
    (net (code "10") (name "/ERXER") (class "Default")
      (node (ref "U7") (pin "10") (pinfunction "RXER_10") (pintype "passive"))
    )
    (net (code "11") (name "/ETH_RESET") (class "Default")
      (node (ref "U7") (pin "15") (pinfunction "~{RST}_15") (pintype "passive"))
    )
    (net (code "12") (name "/ETXD0") (class "Default")
      (node (ref "U7") (pin "17") (pinfunction "TXD0_17") (pintype "passive"))
    )
    (net (code "13") (name "/ETXD1") (class "Default")
      (node (ref "U7") (pin "18") (pinfunction "TXD1_18") (pintype "passive"))
    )
    (net (code "14") (name "/ETXEN") (class "Default")
      (node (ref "U7") (pin "16") (pinfunction "TXEN_16") (pintype "passive"))
    )
    (net (code "15") (name "/I2C0_SCL") (class "Default")
      (node (ref "R56") (pin "1") (pinfunction "1_1") (pintype "passive"))
      (node (ref "U12") (pin "8") (pinfunction "SCK/SCL/TX_8") (pintype "passive"))
      (node (ref "U13") (pin "5") (pinfunction "SCL_5") (pintype "input"))
    )
    (net (code "16") (name "/I2C0_SDA") (class "Default")
      (node (ref "R57") (pin "1") (pinfunction "1_1") (pintype "passive"))
      (node (ref "U12") (pin "10") (pinfunction "SDI/SDA/RX_10") (pintype "passive"))
      (node (ref "U13") (pin "3") (pinfunction "SDA_3") (pintype "bidirectional"))
    )
    (net (code "17") (name "/I2S0_RXD0") (class "Default")
      (node (ref "U8") (pin "6") (pinfunction "ADCOUT_6") (pintype "passive"))
    )
    (net (code "18") (name "/I2S0_TXD0") (class "Default")
      (node (ref "U8") (pin "7") (pinfunction "DACIN_7") (pintype "passive"))
    )
    (net (code "19") (name "/I2S0_TX_BCLK") (class "Default")
      (node (ref "U8") (pin "9") (pinfunction "BCLK_9") (pintype "passive"))
    )
    (net (code "20") (name "/I2S0_TX_FS") (class "Default")
      (node (ref "U8") (pin "8") (pinfunction "FS_8") (pintype "passive"))
    )
    (net (code "21") (name "/MDC") (class "Default")
      (node (ref "U7") (pin "13") (pinfunction "MDC_13") (pintype "passive"))
    )
    (net (code "22") (name "/MDIO") (class "Default")
      (node (ref "U7") (pin "12") (pinfunction "MDIO_12") (pintype "passive"))
    )
    (net (code "23") (name "/MIC+") (class "Default")
      (node (ref "C69") (pin "1") (pinfunction "1_1") (pintype "passive"))
      (node (ref "U8") (pin "1") (pinfunction "MIC+_1") (pintype "passive"))
    )
    (net (code "24") (name "/MIC-") (class "Default")
      (node (ref "C70") (pin "1") (pinfunction "1_1") (pintype "passive"))
      (node (ref "U8") (pin "20") (pinfunction "MIC-_20") (pintype "passive"))
    )
    (net (code "25") (name "/OTG_BUS") (class "Default")
      (node (ref "C102") (pin "1") (pinfunction "1_1") (pintype "passive"))
      (node (ref "L10") (pin "2") (pinfunction "2_2") (pintype "passive"))
      (node (ref "X6") (pin "1") (pinfunction "VBUS_1") (pintype "power_in"))
    )
    (net (code "26") (name "/OTG_ID") (class "Default")
      (node (ref "U13") (pin "11") (pinfunction "ID_IN_11") (pintype "input"))
      (node (ref "X6") (pin "4") (pinfunction "DI_4") (pintype "bidirectional"))
    )
    (net (code "27") (name "/OTG_N") (class "Default")
      (node (ref "R55") (pin "1") (pinfunction "1_1") (pintype "passive"))
      (node (ref "U13") (pin "9") (pinfunction "D-_9") (pintype "bidirectional"))
      (node (ref "X6") (pin "2") (pinfunction "D-_2") (pintype "bidirectional"))
    )
    (net (code "28") (name "/OTG_P") (class "Default")
      (node (ref "R54") (pin "1") (pinfunction "1_1") (pintype "passive"))
      (node (ref "U13") (pin "10") (pinfunction "D+_10") (pintype "bidirectional"))
      (node (ref "X6") (pin "3") (pinfunction "D+_3") (pintype "bidirectional"))
    )
    (net (code "29") (name "/REF50MHZ") (class "Default")
      (node (ref "U7") (pin "14") (pinfunction "REFCLKO_14") (pintype "passive"))
    )
    (net (code "30") (name "/RX_N") (class "Default")
      (node (ref "R31") (pin "1") (pinfunction "1_1") (pintype "passive"))
      (node (ref "U7") (pin "22") (pinfunction "RXN_22") (pintype "passive"))
      (node (ref "X3") (pin "6") (pinfunction "RD-_6") (pintype "passive"))
    )
    (net (code "31") (name "/RX_P") (class "Default")
      (node (ref "R32") (pin "1") (pinfunction "1_1") (pintype "passive"))
      (node (ref "U7") (pin "23") (pinfunction "RXP_23") (pintype "passive"))
      (node (ref "X3") (pin "3") (pinfunction "RD+_3") (pintype "passive"))
    )
    (net (code "32") (name "/SD_CLK") (class "Default")
      (node (ref "X2") (pin "5") (pinfunction "CLK/SCLK_5") (pintype "passive"))
    )
    (net (code "33") (name "/SD_CMD") (class "Default")
      (node (ref "X2") (pin "3") (pinfunction "CMD/DI_3") (pintype "passive"))
    )
    (net (code "34") (name "/SD_D0") (class "Default")
      (node (ref "X2") (pin "7") (pinfunction "DAT0/DO_7") (pintype "passive"))
    )
    (net (code "35") (name "/SD_D1") (class "Default")
      (node (ref "X2") (pin "8") (pinfunction "DAT1_8") (pintype "passive"))
    )
    (net (code "36") (name "/SD_D2") (class "Default")
      (node (ref "X2") (pin "1") (pinfunction "DAT2_1") (pintype "passive"))
    )
    (net (code "37") (name "/SD_D3") (class "Default")
      (node (ref "X2") (pin "2") (pinfunction "CD/DAT3/CS_2") (pintype "passive"))
    )
    (net (code "38") (name "/SPI1_PCS1") (class "Default")
      (node (ref "U8") (pin "10") (pinfunction "~{CS}_10") (pintype "passive"))
    )
    (net (code "39") (name "/SPI1_SCK") (class "Default")
      (node (ref "U8") (pin "11") (pinfunction "SCLK_11") (pintype "passive"))
    )
    (net (code "40") (name "/SPI1_SOUT") (class "Default")
      (node (ref "U8") (pin "12") (pinfunction "SDIO_12") (pintype "passive"))
    )
    (net (code "41") (name "/SPKOUT+") (class "Default")
      (node (ref "U8") (pin "14") (pinfunction "SPKOUT+_14") (pintype "passive"))
    )
    (net (code "42") (name "/SPKOUT-") (class "Default")
      (node (ref "U8") (pin "16") (pinfunction "SPKOUT-_16") (pintype "passive"))
    )
    (net (code "43") (name "/TS_X1") (class "Default")
      (node (ref "D6") (pin "1") (pinfunction "C_1") (pintype "passive"))
      (node (ref "U12") (pin "15") (pinfunction "X+_15") (pintype "passive"))
    )
    (net (code "44") (name "/TS_X2") (class "Default")
      (node (ref "D8") (pin "1") (pinfunction "C_1") (pintype "passive"))
      (node (ref "R52") (pin "2") (pinfunction "2_2") (pintype "passive"))
      (node (ref "U12") (pin "16") (pinfunction "X-_16") (pintype "passive"))
    )
    (net (code "45") (name "/TS_Y1") (class "Default")
      (node (ref "D5") (pin "1") (pinfunction "C_1") (pintype "passive"))
      (node (ref "U12") (pin "12") (pinfunction "Y+_12") (pintype "passive"))
    )
    (net (code "46") (name "/TS_Y2") (class "Default")
      (node (ref "D7") (pin "1") (pinfunction "C_1") (pintype "passive"))
      (node (ref "U12") (pin "13") (pinfunction "Y-_13") (pintype "passive"))
    )
    (net (code "47") (name "/TX_N") (class "Default")
      (node (ref "R33") (pin "2") (pinfunction "2_2") (pintype "passive"))
      (node (ref "U7") (pin "20") (pinfunction "TXN_20") (pintype "passive"))
      (node (ref "X3") (pin "2") (pinfunction "TD-_2") (pintype "passive"))
    )
    (net (code "48") (name "/TX_P") (class "Default")
      (node (ref "R34") (pin "2") (pinfunction "2_2") (pintype "passive"))
      (node (ref "U7") (pin "21") (pinfunction "TXP_21") (pintype "passive"))
      (node (ref "X3") (pin "1") (pinfunction "TD+_1") (pintype "passive"))
    )
    (net (code "49") (name "/U1_N") (class "Default")
      (node (ref "R42") (pin "2") (pinfunction "2_2") (pintype "passive"))
      (node (ref "U10") (pin "8") (pinfunction "DM_8") (pintype "bidirectional"))
    )
    (net (code "50") (name "/U1_P") (class "Default")
      (node (ref "R43") (pin "2") (pinfunction "2_2") (pintype "passive"))
      (node (ref "U10") (pin "7") (pinfunction "DP_7") (pintype "bidirectional"))
    )
    (net (code "51") (name "/U2_N") (class "Default")
      (node (ref "D3") (pin "2") (pinfunction "A_2") (pintype "passive"))
      (node (ref "R42") (pin "1") (pinfunction "1_1") (pintype "passive"))
      (node (ref "X4") (pin "2") (pinfunction "D-_2") (pintype "bidirectional"))
    )
    (net (code "52") (name "/U2_P") (class "Default")
      (node (ref "D4") (pin "2") (pinfunction "A_2") (pintype "passive"))
      (node (ref "R43") (pin "1") (pinfunction "1_1") (pintype "passive"))
      (node (ref "X4") (pin "3") (pinfunction "D+_3") (pintype "bidirectional"))
    )
    (net (code "53") (name "/ULPI_CLK") (class "Default")
      (node (ref "U10") (pin "14") (pinfunction "CLKOUT_14") (pintype "output"))
    )
    (net (code "54") (name "/ULPI_DATA0") (class "Default")
      (node (ref "U10") (pin "24") (pinfunction "DATA[0]_24") (pintype "bidirectional"))
    )
    (net (code "55") (name "/ULPI_DATA1") (class "Default")
      (node (ref "U10") (pin "23") (pinfunction "DATA[1]_23") (pintype "bidirectional"))
    )
    (net (code "56") (name "/ULPI_DATA2") (class "Default")
      (node (ref "U10") (pin "22") (pinfunction "DATA[2]_22") (pintype "bidirectional"))
    )
    (net (code "57") (name "/ULPI_DATA3") (class "Default")
      (node (ref "U10") (pin "21") (pinfunction "DATA[3]_21") (pintype "bidirectional"))
    )
    (net (code "58") (name "/ULPI_DATA4") (class "Default")
      (node (ref "U10") (pin "20") (pinfunction "DATA[4]_20") (pintype "bidirectional"))
    )
    (net (code "59") (name "/ULPI_DATA5") (class "Default")
      (node (ref "U10") (pin "19") (pinfunction "DATA[5]_19") (pintype "bidirectional"))
    )
    (net (code "60") (name "/ULPI_DATA6") (class "Default")
      (node (ref "U10") (pin "18") (pinfunction "DATA[6]_18") (pintype "bidirectional"))
    )
    (net (code "61") (name "/ULPI_DATA7") (class "Default")
      (node (ref "U10") (pin "17") (pinfunction "DATA[7]_17") (pintype "bidirectional"))
    )
    (net (code "62") (name "/ULPI_DIR") (class "Default")
      (node (ref "U10") (pin "12") (pinfunction "DIR_12") (pintype "output"))
    )
    (net (code "63") (name "/ULPI_NXT") (class "Default")
      (node (ref "U10") (pin "11") (pinfunction "NXT_11") (pintype "output"))
    )
    (net (code "64") (name "/ULPI_RESET") (class "Default")
      (node (ref "U10") (pin "9") (pinfunction "RESET_9") (pintype "input"))
    )
    (net (code "65") (name "/ULPI_STP") (class "Default")
      (node (ref "U10") (pin "13") (pinfunction "STP_13") (pintype "input"))
    )
    (net (code "66") (name "/USB1_N") (class "Default")
      (node (ref "R55") (pin "2") (pinfunction "2_2") (pintype "passive"))
    )
    (net (code "67") (name "/USB1_P") (class "Default")
      (node (ref "R54") (pin "2") (pinfunction "2_2") (pintype "passive"))
    )
    (net (code "68") (name "/USB_FLG") (class "Default")
      (node (ref "U11") (pin "3") (pinfunction "FLGB_3") (pintype "output"))
    )
    (net (code "69") (name "/USB_ID_OUT") (class "Default")
      (node (ref "U13") (pin "7") (pinfunction "ID_OUT_7") (pintype "output"))
    )
    (net (code "70") (name "/USB_INT") (class "Default")
      (node (ref "U13") (pin "6") (pinfunction "~{INT}_6") (pintype "output"))
    )
    (net (code "71") (name "ETH_VDD") (class "Default")
      (node (ref "C56") (pin "1") (pinfunction "1_1") (pintype "passive"))
      (node (ref "C57") (pin "1") (pinfunction "1_1") (pintype "passive"))
      (node (ref "C58") (pin "1") (pinfunction "1_1") (pintype "passive"))
      (node (ref "C59") (pin "1") (pinfunction "1_1") (pintype "passive"))
      (node (ref "C60") (pin "1") (pinfunction "1_1") (pintype "passive"))
      (node (ref "L7") (pin "1") (pinfunction "1_1") (pintype "passive"))
      (node (ref "R31") (pin "2") (pinfunction "2_2") (pintype "passive"))
      (node (ref "R32") (pin "2") (pinfunction "2_2") (pintype "passive"))
      (node (ref "R33") (pin "1") (pinfunction "1_1") (pintype "passive"))
      (node (ref "R34") (pin "1") (pinfunction "1_1") (pintype "passive"))
      (node (ref "U7") (pin "1") (pinfunction "VDD2A_1") (pintype "power_in"))
      (node (ref "U7") (pin "19") (pinfunction "VDD1A_19") (pintype "passive"))
      (node (ref "X3") (pin "4") (pinfunction "CT_4") (pintype "passive"))
      (node (ref "X3") (pin "5") (pinfunction "CT_5") (pintype "passive"))
    )
    (net (code "72") (name "GND") (class "Default")
      (node (ref "C100") (pin "1") (pinfunction "1_1") (pintype "passive"))
      (node (ref "C101") (pin "2") (pinfunction "2_2") (pintype "passive"))
      (node (ref "C102") (pin "2") (pinfunction "2_2") (pintype "passive"))
      (node (ref "C103") (pin "2") (pinfunction "2_2") (pintype "passive"))
      (node (ref "C104") (pin "2") (pinfunction "2_2") (pintype "passive"))
      (node (ref "C106") (pin "1") (pinfunction "1_1") (pintype "passive"))
      (node (ref "C108") (pin "2") (pinfunction "2_2") (pintype "passive"))
      (node (ref "C56") (pin "2") (pinfunction "2_2") (pintype "passive"))
      (node (ref "C57") (pin "2") (pinfunction "2_2") (pintype "passive"))
      (node (ref "C58") (pin "2") (pinfunction "2_2") (pintype "passive"))
      (node (ref "C59") (pin "2") (pinfunction "2_2") (pintype "passive"))
      (node (ref "C60") (pin "2") (pinfunction "2_2") (pintype "passive"))
      (node (ref "C63") (pin "1") (pinfunction "1_1") (pintype "passive"))
      (node (ref "C64") (pin "1") (pinfunction "1_1") (pintype "passive"))
      (node (ref "C65") (pin "2") (pinfunction "2_2") (pintype "passive"))
      (node (ref "C66") (pin "2") (pinfunction "2_2") (pintype "passive"))
      (node (ref "C70") (pin "2") (pinfunction "2_2") (pintype "passive"))
      (node (ref "C71") (pin "1") (pinfunction "1_1") (pintype "passive"))
      (node (ref "C72") (pin "1") (pinfunction "1_1") (pintype "passive"))
      (node (ref "C73") (pin "1") (pinfunction "1_1") (pintype "passive"))
      (node (ref "C74") (pin "2") (pinfunction "2_2") (pintype "passive"))
      (node (ref "C75") (pin "1") (pinfunction "1_1") (pintype "passive"))
      (node (ref "C76") (pin "2") (pinfunction "2_2") (pintype "passive"))
      (node (ref "C77") (pin "2") (pinfunction "2_2") (pintype "passive"))
      (node (ref "C78") (pin "2") (pinfunction "2_2") (pintype "passive"))
      (node (ref "C79") (pin "2") (pinfunction "2_2") (pintype "passive"))
      (node (ref "C80") (pin "2") (pinfunction "2_2") (pintype "passive"))
      (node (ref "C81") (pin "1") (pinfunction "1_1") (pintype "passive"))
      (node (ref "C83") (pin "2") (pinfunction "2_2") (pintype "passive"))
      (node (ref "C88") (pin "1") (pinfunction "1_1") (pintype "passive"))
      (node (ref "C89") (pin "1") (pinfunction "1_1") (pintype "passive"))
      (node (ref "C90") (pin "1") (pinfunction "1_1") (pintype "passive"))
      (node (ref "C91") (pin "2") (pinfunction "2_2") (pintype "passive"))
      (node (ref "C92") (pin "1") (pinfunction "1_1") (pintype "passive"))
      (node (ref "C93") (pin "2") (pinfunction "2_2") (pintype "passive"))
      (node (ref "C94") (pin "1") (pinfunction "1_1") (pintype "passive"))
      (node (ref "C95") (pin "1") (pinfunction "1_1") (pintype "passive"))
      (node (ref "C96") (pin "2") (pinfunction "2_2") (pintype "passive"))
      (node (ref "C97") (pin "1") (pinfunction "1_1") (pintype "passive"))
      (node (ref "C98") (pin "1") (pinfunction "1_1") (pintype "passive"))
      (node (ref "C99") (pin "2") (pinfunction "2_2") (pintype "passive"))
      (node (ref "D3") (pin "1") (pinfunction "C_1") (pintype "passive"))
      (node (ref "D4") (pin "1") (pinfunction "C_1") (pintype "passive"))
      (node (ref "D5") (pin "2") (pinfunction "A_2") (pintype "passive"))
      (node (ref "D6") (pin "2") (pinfunction "A_2") (pintype "passive"))
      (node (ref "D7") (pin "2") (pinfunction "A_2") (pintype "passive"))
      (node (ref "D8") (pin "2") (pinfunction "A_2") (pintype "passive"))
      (node (ref "L11") (pin "1") (pinfunction "1_1") (pintype "passive"))
      (node (ref "L9") (pin "1") (pinfunction "1_1") (pintype "passive"))
      (node (ref "MIC1") (pin "2") (pinfunction "GND_2") (pintype "passive"))
      (node (ref "R37") (pin "2") (pinfunction "2_2") (pintype "passive"))
      (node (ref "R39") (pin "1") (pinfunction "1_1") (pintype "passive"))
      (node (ref "R40") (pin "1") (pinfunction "1_1") (pintype "passive"))
      (node (ref "R46") (pin "1") (pinfunction "1_1") (pintype "passive"))
      (node (ref "R53") (pin "1") (pinfunction "1_1") (pintype "passive"))
      (node (ref "U10") (pin "1") (pinfunction "GND_1") (pintype "power_in"))
      (node (ref "U10") (pin "2") (pinfunction "GND_2") (pintype "power_in"))
      (node (ref "U10") (pin "33") (pinfunction "GND_FLAG_33") (pintype "passive"))
      (node (ref "U11") (pin "6") (pinfunction "GND_6") (pintype "passive"))
      (node (ref "U12") (pin "1") (pinfunction "M2_1") (pintype "passive"))
      (node (ref "U12") (pin "11") (pinfunction "SX+_11") (pintype "passive"))
      (node (ref "U12") (pin "14") (pinfunction "5WSX-_14") (pintype "passive"))
      (node (ref "U12") (pin "17") (pinfunction "GND_17") (pintype "passive"))
      (node (ref "U12") (pin "19") (pinfunction "M1_19") (pintype "passive"))
      (node (ref "U12") (pin "20") (pinfunction "SY-_20") (pintype "passive"))
      (node (ref "U12") (pin "21") (pinfunction "PAD_21") (pintype "passive"))
      (node (ref "U12") (pin "4") (pinfunction "SY+_4") (pintype "passive"))
      (node (ref "U12") (pin "5") (pinfunction "SS_5") (pintype "passive"))
      (node (ref "U13") (pin "13") (pinfunction "GND_13") (pintype "power_in"))
      (node (ref "U13") (pin "4") (pinfunction "ADD_4") (pintype "input"))
      (node (ref "U7") (pin "25") (pinfunction "VSS_25") (pintype "passive"))
      (node (ref "U8") (pin "15") (pinfunction "VSSSPK_15") (pintype "passive"))
      (node (ref "U8") (pin "21") (pinfunction "VSSA_21") (pintype "passive"))
      (node (ref "U8") (pin "3") (pinfunction "VSSA_3") (pintype "passive"))
      (node (ref "U8") (pin "5") (pinfunction "VSSD_5") (pintype "passive"))
      (node (ref "X2") (pin "10") (pinfunction "WP_10") (pintype "passive"))
      (node (ref "X2") (pin "11") (pinfunction "GND_11") (pintype "passive"))
      (node (ref "X2") (pin "12") (pinfunction "GND_12") (pintype "passive"))
      (node (ref "X2") (pin "6") (pinfunction "VSS2_6") (pintype "passive"))
      (node (ref "X2") (pin "9") (pintype "passive"))
      (node (ref "X3") (pin "10") (pinfunction "10_10") (pintype "passive"))
      (node (ref "X3") (pin "11") (pinfunction "11_11") (pintype "passive"))
      (node (ref "X3") (pin "13") (pinfunction "13_13") (pintype "passive"))
      (node (ref "X3") (pin "14") (pinfunction "14_14") (pintype "passive"))
      (node (ref "X3") (pin "8") (pinfunction "GND_8") (pintype "passive"))
      (node (ref "X4") (pin "5") (pinfunction "GND_5") (pintype "power_in"))
      (node (ref "X6") (pin "5") (pinfunction "GND_5") (pintype "power_in"))
    )
    (net (code "73") (name "Net-(C90-Pad2)") (class "Default")
      (node (ref "C90") (pin "2") (pinfunction "2_2") (pintype "passive"))
      (node (ref "C91") (pin "1") (pinfunction "1_1") (pintype "passive"))
      (node (ref "U10") (pin "15") (pinfunction "VDD1.8_15") (pintype "power_in"))
      (node (ref "U10") (pin "26") (pinfunction "VDD1.8_26") (pintype "power_in"))
    )
    (net (code "74") (name "Net-(L9-Pad2)") (class "Default")
      (node (ref "L9") (pin "2") (pinfunction "2_2") (pintype "passive"))
      (node (ref "X4") (pin "S1") (pinfunction "SHLD_S1") (pintype "passive"))
      (node (ref "X4") (pin "S2") (pinfunction "SHLD_S2") (pintype "passive"))
      (node (ref "X4") (pin "S3") (pinfunction "SHLD_S3") (pintype "passive"))
      (node (ref "X4") (pin "S4") (pinfunction "SHLD_S4") (pintype "passive"))
    )
    (net (code "75") (name "Net-(L11-Pad2)") (class "Default")
      (node (ref "L11") (pin "2") (pinfunction "2_2") (pintype "passive"))
      (node (ref "X6") (pin "S1") (pinfunction "SHLD_S1") (pintype "passive"))
      (node (ref "X6") (pin "S2") (pinfunction "SHLD_S2") (pintype "passive"))
      (node (ref "X6") (pin "S3") (pinfunction "SHLD_S3") (pintype "passive"))
      (node (ref "X6") (pin "S4") (pinfunction "SHLD_S4") (pintype "passive"))
    )
    (net (code "76") (name "Net-(MIC1-Out)") (class "Default")
      (node (ref "C69") (pin "2") (pinfunction "2_2") (pintype "passive"))
      (node (ref "MIC1") (pin "1") (pinfunction "Out_1") (pintype "passive"))
    )
    (net (code "77") (name "Net-(R38-Pad1)") (class "Default")
      (node (ref "R38") (pin "1") (pinfunction "1_1") (pintype "passive"))
      (node (ref "R39") (pin "2") (pinfunction "2_2") (pintype "passive"))
    )
    (net (code "78") (name "Net-(R51-Pad2)") (class "Default")
      (node (ref "R51") (pin "2") (pinfunction "2_2") (pintype "passive"))
      (node (ref "R52") (pin "1") (pinfunction "1_1") (pintype "passive"))
    )
    (net (code "79") (name "Net-(U7-LED1)") (class "Default")
      (node (ref "R35") (pin "2") (pinfunction "2_2") (pintype "passive"))
      (node (ref "U7") (pin "3") (pinfunction "LED1_3") (pintype "passive"))
    )
    (net (code "80") (name "Net-(U7-LED2)") (class "Default")
      (node (ref "R36") (pin "2") (pinfunction "2_2") (pintype "passive"))
      (node (ref "R37") (pin "1") (pinfunction "1_1") (pintype "passive"))
      (node (ref "U7") (pin "2") (pinfunction "LED2_2") (pintype "power_in"))
    )
    (net (code "81") (name "Net-(U7-RBIAS)") (class "Default")
      (node (ref "C74") (pin "1") (pinfunction "1_1") (pintype "passive"))
      (node (ref "R38") (pin "2") (pinfunction "2_2") (pintype "passive"))
      (node (ref "U7") (pin "24") (pinfunction "RBIAS_24") (pintype "passive"))
    )
    (net (code "82") (name "Net-(U7-VDDCR)") (class "Default")
      (node (ref "C75") (pin "2") (pinfunction "2_2") (pintype "passive"))
      (node (ref "C76") (pin "1") (pinfunction "1_1") (pintype "passive"))
      (node (ref "U7") (pin "6") (pinfunction "VDDCR_6") (pintype "passive"))
    )
    (net (code "83") (name "Net-(U7-XTAL1)") (class "Default")
      (node (ref "C79") (pin "1") (pinfunction "1_1") (pintype "passive"))
      (node (ref "U7") (pin "5") (pinfunction "XTAL1_5") (pintype "passive"))
      (node (ref "Z3") (pin "2") (pinfunction "2_2") (pintype "passive"))
    )
    (net (code "84") (name "Net-(U7-XTAL2)") (class "Default")
      (node (ref "C78") (pin "1") (pinfunction "1_1") (pintype "passive"))
      (node (ref "U7") (pin "4") (pinfunction "XTAL2_4") (pintype "passive"))
      (node (ref "Z3") (pin "1") (pinfunction "1_1") (pintype "passive"))
    )
    (net (code "85") (name "Net-(U8-VREF)") (class "Default")
      (node (ref "C73") (pin "2") (pinfunction "2_2") (pintype "passive"))
      (node (ref "U8") (pin "19") (pinfunction "VREF_19") (pintype "passive"))
    )
    (net (code "86") (name "Net-(U10-CPEN)") (class "Default")
      (node (ref "U10") (pin "3") (pinfunction "CPEN_3") (pintype "output"))
      (node (ref "U11") (pin "1") (pinfunction "ENA_1") (pintype "input"))
    )
    (net (code "87") (name "Net-(U10-EXTVBUS)") (class "Default")
      (node (ref "R48") (pin "2") (pinfunction "2_2") (pintype "passive"))
      (node (ref "U10") (pin "10") (pinfunction "EXTVBUS_10") (pintype "input"))
      (node (ref "U11") (pin "2") (pinfunction "FLGA_2") (pintype "output"))
    )
    (net (code "88") (name "Net-(U10-ID)") (class "Default")
      (node (ref "R41") (pin "1") (pinfunction "1_1") (pintype "passive"))
      (node (ref "U10") (pin "5") (pinfunction "ID_5") (pintype "input"))
      (node (ref "X4") (pin "4") (pinfunction "DI_4") (pintype "bidirectional"))
    )
    (net (code "89") (name "Net-(U10-RBIAS)") (class "Default")
      (node (ref "R46") (pin "2") (pinfunction "2_2") (pintype "passive"))
      (node (ref "U10") (pin "32") (pinfunction "RBIAS_32") (pintype "passive"))
    )
    (net (code "90") (name "Net-(U10-REG_EN)") (class "Default")
      (node (ref "R50") (pin "1") (pinfunction "1_1") (pintype "passive"))
      (node (ref "U10") (pin "31") (pinfunction "REG_EN_31") (pintype "bidirectional"))
    )
    (net (code "91") (name "Net-(U10-VBUS)") (class "Default")
      (node (ref "R44") (pin "2") (pinfunction "2_2") (pintype "passive"))
      (node (ref "U10") (pin "4") (pinfunction "VBUS_4") (pintype "bidirectional"))
    )
    (net (code "92") (name "Net-(U10-VDDA1.8)") (class "Default")
      (node (ref "C98") (pin "2") (pinfunction "2_2") (pintype "passive"))
      (node (ref "C99") (pin "1") (pinfunction "1_1") (pintype "passive"))
      (node (ref "U10") (pin "29") (pinfunction "VDDA1.8_29") (pintype "power_in"))
    )
    (net (code "93") (name "Net-(U10-XI)") (class "Default")
      (node (ref "C88") (pin "2") (pinfunction "2_2") (pintype "passive"))
      (node (ref "R45") (pin "2") (pinfunction "2_2") (pintype "passive"))
      (node (ref "U10") (pin "28") (pinfunction "XI_28") (pintype "input"))
      (node (ref "Z4") (pin "2") (pinfunction "2_2") (pintype "passive"))
    )
    (net (code "94") (name "Net-(U10-XO)") (class "Default")
      (node (ref "C89") (pin "2") (pinfunction "2_2") (pintype "passive"))
      (node (ref "R45") (pin "1") (pinfunction "1_1") (pintype "passive"))
      (node (ref "U10") (pin "27") (pinfunction "XO_27") (pintype "output"))
      (node (ref "Z4") (pin "1") (pinfunction "1_1") (pintype "passive"))
    )
    (net (code "95") (name "Net-(U11-ENB)") (class "Default")
      (node (ref "R49") (pin "1") (pinfunction "1_1") (pintype "passive"))
      (node (ref "U11") (pin "4") (pinfunction "ENB_4") (pintype "input"))
    )
    (net (code "96") (name "Net-(U11-OUTA)") (class "Default")
      (node (ref "C80") (pin "1") (pinfunction "1_1") (pintype "passive"))
      (node (ref "C81") (pin "2") (pinfunction "2_2") (pintype "passive"))
      (node (ref "L8") (pin "1") (pinfunction "1_1") (pintype "passive"))
      (node (ref "R40") (pin "2") (pinfunction "2_2") (pintype "passive"))
      (node (ref "R44") (pin "1") (pinfunction "1_1") (pintype "passive"))
      (node (ref "U11") (pin "8") (pinfunction "OUTA_8") (pintype "passive"))
    )
    (net (code "97") (name "Net-(U11-OUTB)") (class "Default")
      (node (ref "R104") (pin "2") (pinfunction "2_2") (pintype "passive"))
      (node (ref "U11") (pin "5") (pinfunction "OUTB_5") (pintype "passive"))
    )
    (net (code "98") (name "Net-(U12-WAKE)") (class "Default")
      (node (ref "R51") (pin "1") (pinfunction "1_1") (pintype "passive"))
      (node (ref "U12") (pin "2") (pinfunction "WAKE_2") (pintype "passive"))
    )
    (net (code "99") (name "Net-(U13-C+)") (class "Default")
      (node (ref "C105") (pin "1") (pinfunction "1_1") (pintype "passive"))
      (node (ref "U13") (pin "15") (pinfunction "C+_15") (pintype "power_in"))
    )
    (net (code "100") (name "Net-(U13-C-)") (class "Default")
      (node (ref "C105") (pin "2") (pinfunction "2_2") (pintype "passive"))
      (node (ref "U13") (pin "14") (pinfunction "C-_14") (pintype "power_in"))
    )
    (net (code "101") (name "Net-(U13-VBUS)") (class "Default")
      (node (ref "R103") (pin "1") (pinfunction "1_1") (pintype "passive"))
      (node (ref "U13") (pin "16") (pinfunction "VBUS_16") (pintype "power_in"))
    )
    (net (code "102") (name "Net-(X4-VBUS)") (class "Default")
      (node (ref "C83") (pin "1") (pinfunction "1_1") (pintype "passive"))
      (node (ref "L8") (pin "2") (pinfunction "2_2") (pintype "passive"))
      (node (ref "X4") (pin "1") (pinfunction "VBUS_1") (pintype "power_in"))
    )
    (net (code "103") (name "USB_VBUS") (class "Default")
      (node (ref "C100") (pin "2") (pinfunction "2_2") (pintype "passive"))
      (node (ref "C101") (pin "1") (pinfunction "1_1") (pintype "passive"))
      (node (ref "L10") (pin "1") (pinfunction "1_1") (pintype "passive"))
      (node (ref "R103") (pin "2") (pinfunction "2_2") (pintype "passive"))
      (node (ref "R104") (pin "1") (pinfunction "1_1") (pintype "passive"))
      (node (ref "R53") (pin "2") (pinfunction "2_2") (pintype "passive"))
    )
    (net (code "104") (name "unconnected-(U12-NC-Pad7)") (class "Default")
      (node (ref "U12") (pin "7") (pinfunction "NC_7") (pintype "passive"))
    )
    (net (code "105") (name "unconnected-(U12-NC-Pad9)") (class "Default")
      (node (ref "U12") (pin "9") (pinfunction "NC_9") (pintype "passive"))
    )
    (net (code "106") (name "unconnected-(U12-SDO-Pad6)") (class "Default")
      (node (ref "U12") (pin "6") (pinfunction "SDO_6") (pintype "passive"))
    )
    (net (code "107") (name "unconnected-(U12-SIQ-Pad3)") (class "Default")
      (node (ref "U12") (pin "3") (pinfunction "SIQ_3") (pintype "passive"))
    )
  )
)
